# magspoof.net
KiCad netlist of a schematic drawn in EAGLE
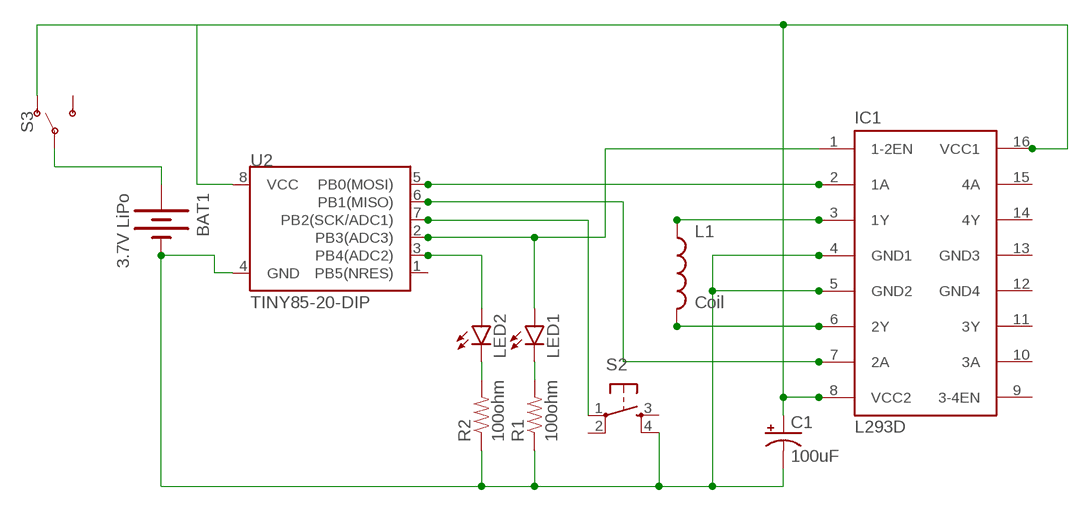
[diagram p0: schematic, sheet 1]

(export (version "E")
  (design (tool "Eeschema 10.0.6"))
  (components
    (comp (ref "BAT1")
      (value "3.7V LiPo")
      (footprint "eagle-import:LIPO-110-TABS")
      (libsource (lib "eagle-import") (part "BATTERYLIPO-TABS"))
    )
    (comp (ref "C1")
      (value "100uF")
      (footprint "eagle-import:CPOL-RADIAL-100UF-25V")
      (libsource (lib "eagle-import") (part "CAP_POLPTH1"))
    )
    (comp (ref "IC1")
      (value "L293D")
      (footprint "eagle-import:DIL16")
      (libsource (lib "eagle-import") (part "L293D"))
    )
    (comp (ref "L1")
      (value "Coil")
      (footprint "eagle-import:AXIAL-0.6")
      (libsource (lib "eagle-import") (part "INDUCTORAXIAL-0.6"))
    )
    (comp (ref "LED1")
      (value "LED-3MM-NO_SILK")
      (footprint "eagle-import:LED3MM-NS")
      (libsource (lib "eagle-import") (part "LED-3MM-NO_SILK"))
    )
    (comp (ref "LED2")
      (value "LED-3MM-NO_SILK")
      (footprint "eagle-import:LED3MM-NS")
      (libsource (lib "eagle-import") (part "LED-3MM-NO_SILK"))
    )
    (comp (ref "R1")
      (value "100ohm")
      (footprint "eagle-import:AXIAL-0.3")
      (libsource (lib "eagle-import") (part "RESISTORAXIAL-0.3"))
    )
    (comp (ref "R2")
      (value "100ohm")
      (footprint "eagle-import:AXIAL-0.3")
      (libsource (lib "eagle-import") (part "RESISTORAXIAL-0.3"))
    )
    (comp (ref "S2")
      (value "TAC_SWITCHPTH")
      (footprint "eagle-import:TACTILE-PTH")
      (libsource (lib "eagle-import") (part "TAC_SWITCHPTH"))
    )
    (comp (ref "S3")
      (value "SWITCH-SPDT-PTH-11.6X4.0MM")
      (footprint "eagle-import:SWITCH_SPDT_PTH_11.6X4.0MM")
      (libsource (lib "eagle-import") (part "SWITCH-SPDT-PTH-11.6X4.0MM"))
    )
    (comp (ref "U2")
      (value "TINY85-20-DIP")
      (footprint "eagle-import:DIP08_MCU")
      (libsource (lib "eagle-import") (part "ATTINY45TINY85-20-DIP"))
    )
  )
  (nets
    (net (code "1") (name "/GND3") (class "Default")
      (node (ref "IC1") (pin "13") (pinfunction "GND3_13") (pintype "power_in"))
    )
    (net (code "2") (name "/GND4") (class "Default")
      (node (ref "IC1") (pin "12") (pinfunction "GND4_12") (pintype "power_in"))
    )
    (net (code "3") (name "Net-(C1-+)") (class "Default")
      (node (ref "C1") (pin "1") (pinfunction "+_1") (pintype "passive"))
      (node (ref "IC1") (pin "16") (pinfunction "VCC1_16") (pintype "power_in"))
      (node (ref "IC1") (pin "8") (pinfunction "VCC2_8") (pintype "power_in"))
      (node (ref "S3") (pin "1") (pinfunction "O_1") (pintype "passive"))
      (node (ref "U2") (pin "8") (pinfunction "VCC_8") (pintype "bidirectional"))
    )
    (net (code "4") (name "Net-(C1--)") (class "Default")
      (node (ref "BAT1") (pin "-") (pinfunction "-_-") (pintype "power_in"))
      (node (ref "C1") (pin "2") (pinfunction "-_2") (pintype "passive"))
      (node (ref "IC1") (pin "4") (pinfunction "GND1_4") (pintype "power_in"))
      (node (ref "IC1") (pin "5") (pinfunction "GND2_5") (pintype "power_in"))
      (node (ref "R1") (pin "P$1") (pinfunction "1_P$1") (pintype "passive"))
      (node (ref "R2") (pin "P$1") (pinfunction "1_P$1") (pintype "passive"))
      (node (ref "S2") (pin "4") (pinfunction "4_4") (pintype "passive"))
      (node (ref "U2") (pin "4") (pinfunction "GND_4") (pintype "bidirectional"))
    )
    (net (code "5") (name "Net-(IC1-1-2EN)") (class "Default")
      (node (ref "IC1") (pin "1") (pinfunction "1-2EN_1") (pintype "input"))
      (node (ref "LED1") (pin "A") (pinfunction "A_A") (pintype "passive"))
      (node (ref "U2") (pin "2") (pinfunction "PB3(ADC3)_2") (pintype "bidirectional"))
    )
    (net (code "6") (name "Net-(IC1-1A)") (class "Default")
      (node (ref "IC1") (pin "2") (pinfunction "1A_2") (pintype "input"))
      (node (ref "U2") (pin "5") (pinfunction "PB0(MOSI)_5") (pintype "bidirectional"))
    )
    (net (code "7") (name "Net-(IC1-1Y)") (class "Default")
      (node (ref "IC1") (pin "3") (pinfunction "1Y_3") (pintype "output"))
      (node (ref "L1") (pin "P$1") (pinfunction "1_P$1") (pintype "passive"))
    )
    (net (code "8") (name "Net-(IC1-2A)") (class "Default")
      (node (ref "IC1") (pin "7") (pinfunction "2A_7") (pintype "input"))
      (node (ref "U2") (pin "6") (pinfunction "PB1(MISO)_6") (pintype "bidirectional"))
    )
    (net (code "9") (name "Net-(IC1-2Y)") (class "Default")
      (node (ref "IC1") (pin "6") (pinfunction "2Y_6") (pintype "output"))
      (node (ref "L1") (pin "P$2") (pinfunction "2_P$2") (pintype "passive"))
    )
    (net (code "10") (name "Net-(LED1-C)") (class "Default")
      (node (ref "LED1") (pin "K") (pinfunction "C_K") (pintype "passive"))
      (node (ref "R1") (pin "P$2") (pinfunction "2_P$2") (pintype "passive"))
    )
    (net (code "11") (name "Net-(LED2-C)") (class "Default")
      (node (ref "LED2") (pin "K") (pinfunction "C_K") (pintype "passive"))
      (node (ref "R2") (pin "P$2") (pinfunction "2_P$2") (pintype "passive"))
    )
    (net (code "12") (name "Net-(S3-P)") (class "Default")
      (node (ref "BAT1") (pin "+") (pinfunction "+_+") (pintype "power_in"))
      (node (ref "S3") (pin "2") (pinfunction "P_2") (pintype "passive"))
    )
    (net (code "13") (name "Net-(U2-PB2(SCK{slash}ADC1))") (class "Default")
      (node (ref "S2") (pin "1") (pinfunction "1_1") (pintype "passive"))
      (node (ref "U2") (pin "7") (pinfunction "PB2(SCK/ADC1)_7") (pintype "bidirectional"))
    )
    (net (code "14") (name "Net-(U2-PB4(ADC2))") (class "Default")
      (node (ref "LED2") (pin "A") (pinfunction "A_A") (pintype "passive"))
      (node (ref "U2") (pin "3") (pinfunction "PB4(ADC2)_3") (pintype "bidirectional"))
    )
    (net (code "15") (name "unconnected-(IC1-3-4EN-Pad9)") (class "Default")
      (node (ref "IC1") (pin "9") (pinfunction "3-4EN_9") (pintype "input"))
    )
    (net (code "16") (name "unconnected-(IC1-3A-Pad10)") (class "Default")
      (node (ref "IC1") (pin "10") (pinfunction "3A_10") (pintype "input"))
    )
    (net (code "17") (name "unconnected-(IC1-3Y-Pad11)") (class "Default")
      (node (ref "IC1") (pin "11") (pinfunction "3Y_11") (pintype "output"))
    )
    (net (code "18") (name "unconnected-(IC1-4A-Pad15)") (class "Default")
      (node (ref "IC1") (pin "15") (pinfunction "4A_15") (pintype "input"))
    )
    (net (code "19") (name "unconnected-(IC1-4Y-Pad14)") (class "Default")
      (node (ref "IC1") (pin "14") (pinfunction "4Y_14") (pintype "output"))
    )
    (net (code "20") (name "unconnected-(S2-Pad2)") (class "Default")
      (node (ref "S2") (pin "2") (pinfunction "2_2") (pintype "passive"))
    )
    (net (code "21") (name "unconnected-(S2-Pad3)") (class "Default")
      (node (ref "S2") (pin "3") (pinfunction "3_3") (pintype "passive"))
    )
    (net (code "22") (name "unconnected-(S3-S-Pad3)") (class "Default")
      (node (ref "S3") (pin "3") (pinfunction "S_3") (pintype "passive"))
    )
    (net (code "23") (name "unconnected-(U2-PB5(NRES)-Pad1)") (class "Default")
      (node (ref "U2") (pin "1") (pinfunction "PB5(NRES)_1") (pintype "bidirectional"))
    )
  )
)
